# in_out.net
KiCad netlist of a schematic drawn in EAGLE
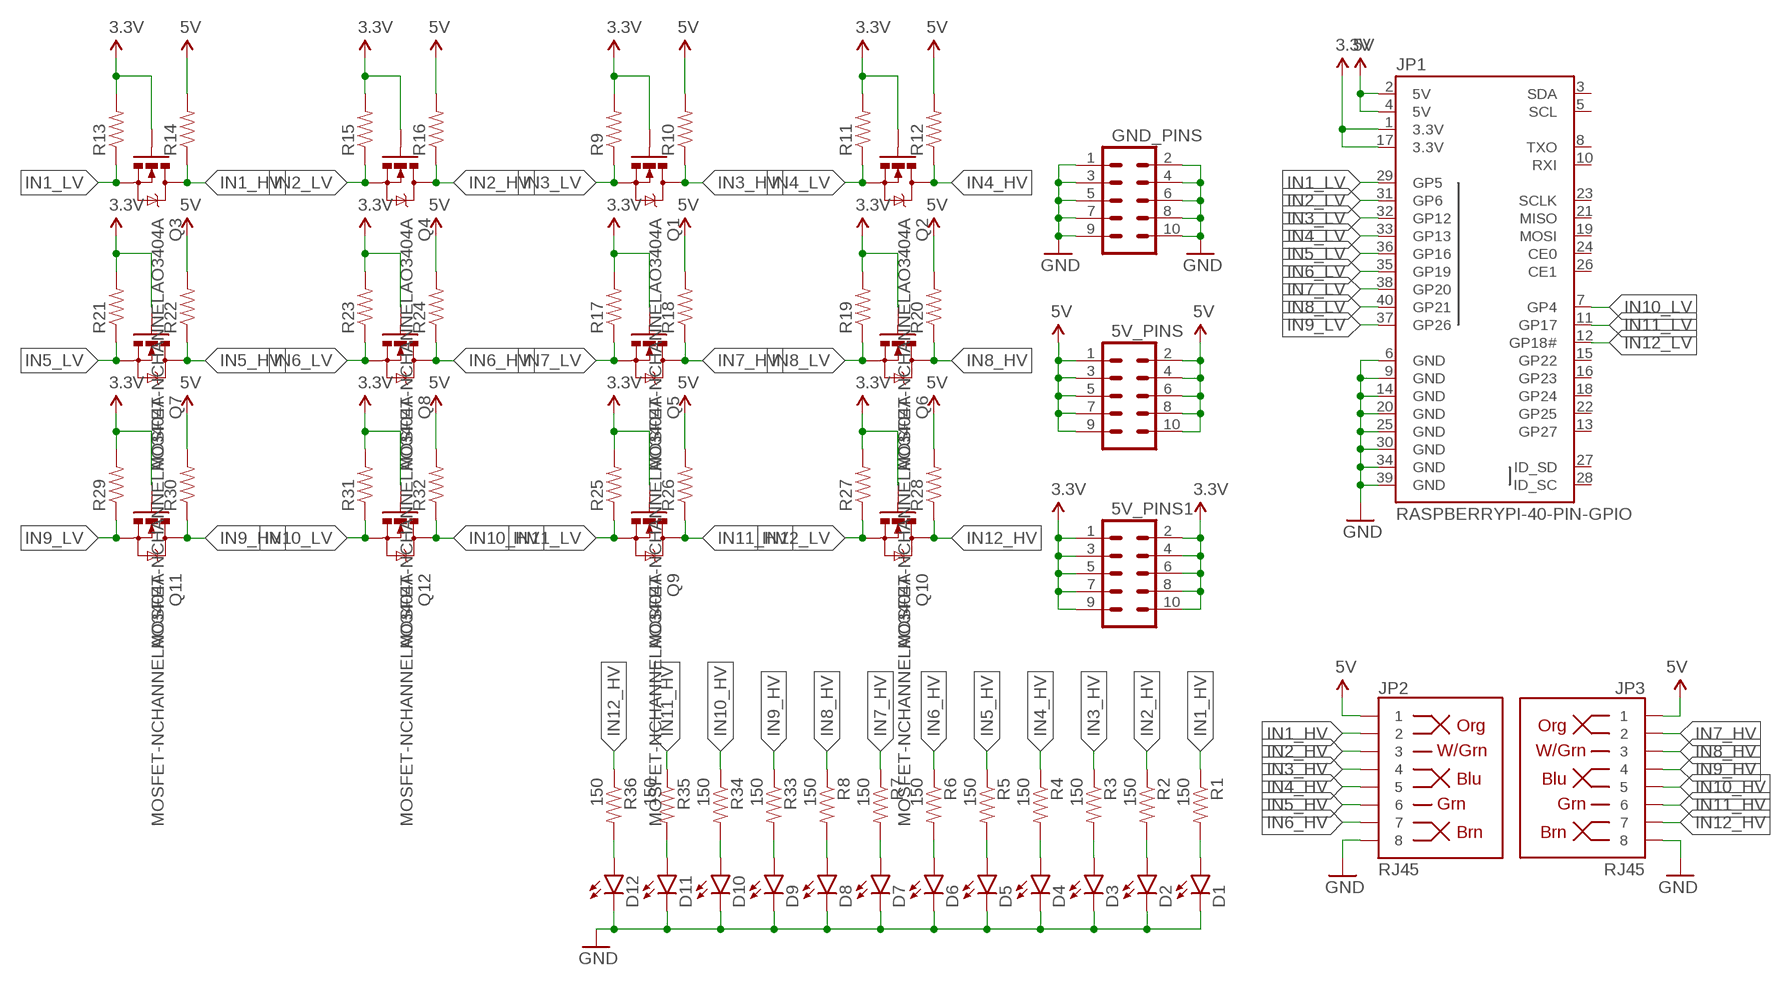
[diagram p0: schematic, sheet 1]

(export (version "E")
  (design (tool "Eeschema 10.0.6"))
  (components
    (comp (ref "5V_PINS")
      (value "M05X2PTH")
      (footprint "eagle-import:AVR_ICSP")
      (libsource (lib "eagle-import") (part "M05X2PTH"))
    )
    (comp (ref "5V_PINS1")
      (value "M05X2PTH")
      (footprint "eagle-import:AVR_ICSP")
      (libsource (lib "eagle-import") (part "M05X2PTH"))
    )
    (comp (ref "D1")
      (value "LED5MM")
      (footprint "eagle-import:LED5MM")
      (libsource (lib "eagle-import") (part "LED5MM"))
    )
    (comp (ref "D2")
      (value "LED5MM")
      (footprint "eagle-import:LED5MM")
      (libsource (lib "eagle-import") (part "LED5MM"))
    )
    (comp (ref "D3")
      (value "LED5MM")
      (footprint "eagle-import:LED5MM")
      (libsource (lib "eagle-import") (part "LED5MM"))
    )
    (comp (ref "D4")
      (value "LED5MM")
      (footprint "eagle-import:LED5MM")
      (libsource (lib "eagle-import") (part "LED5MM"))
    )
    (comp (ref "D5")
      (value "LED5MM")
      (footprint "eagle-import:LED5MM")
      (libsource (lib "eagle-import") (part "LED5MM"))
    )
    (comp (ref "D6")
      (value "LED5MM")
      (footprint "eagle-import:LED5MM")
      (libsource (lib "eagle-import") (part "LED5MM"))
    )
    (comp (ref "D7")
      (value "LED5MM")
      (footprint "eagle-import:LED5MM")
      (libsource (lib "eagle-import") (part "LED5MM"))
    )
    (comp (ref "D8")
      (value "LED5MM")
      (footprint "eagle-import:LED5MM")
      (libsource (lib "eagle-import") (part "LED5MM"))
    )
    (comp (ref "D9")
      (value "LED5MM")
      (footprint "eagle-import:LED5MM")
      (libsource (lib "eagle-import") (part "LED5MM"))
    )
    (comp (ref "D10")
      (value "LED5MM")
      (footprint "eagle-import:LED5MM")
      (libsource (lib "eagle-import") (part "LED5MM"))
    )
    (comp (ref "D11")
      (value "LED5MM")
      (footprint "eagle-import:LED5MM")
      (libsource (lib "eagle-import") (part "LED5MM"))
    )
    (comp (ref "D12")
      (value "LED5MM")
      (footprint "eagle-import:LED5MM")
      (libsource (lib "eagle-import") (part "LED5MM"))
    )
    (comp (ref "GND_PINS")
      (value "M05X2PTH")
      (footprint "eagle-import:AVR_ICSP")
      (libsource (lib "eagle-import") (part "M05X2PTH"))
    )
    (comp (ref "JP1")
      (value "RASPBERRYPI-40-PIN-GPIO")
      (footprint "eagle-import:2X20-SHROUDED")
      (libsource (lib "eagle-import") (part "RASPBERRYPI-40-PIN-GPIO"))
    )
    (comp (ref "JP2")
      (value "RJ45")
      (footprint "eagle-import:RJ45-8")
      (libsource (lib "eagle-import") (part "RJ45-8PTH"))
    )
    (comp (ref "JP3")
      (value "RJ45")
      (footprint "eagle-import:RJ45-8")
      (libsource (lib "eagle-import") (part "RJ45-8PTH"))
    )
    (comp (ref "Q1")
      (value "MOSFET-NCHANNELAO3404A")
      (footprint "eagle-import:SOT23-3")
      (libsource (lib "eagle-import") (part "MOSFET-NCHANNELAO3404A"))
    )
    (comp (ref "Q2")
      (value "MOSFET-NCHANNELAO3404A")
      (footprint "eagle-import:SOT23-3")
      (libsource (lib "eagle-import") (part "MOSFET-NCHANNELAO3404A"))
    )
    (comp (ref "Q3")
      (value "MOSFET-NCHANNELAO3404A")
      (footprint "eagle-import:SOT23-3")
      (libsource (lib "eagle-import") (part "MOSFET-NCHANNELAO3404A"))
    )
    (comp (ref "Q4")
      (value "MOSFET-NCHANNELAO3404A")
      (footprint "eagle-import:SOT23-3")
      (libsource (lib "eagle-import") (part "MOSFET-NCHANNELAO3404A"))
    )
    (comp (ref "Q5")
      (value "MOSFET-NCHANNELAO3404A")
      (footprint "eagle-import:SOT23-3")
      (libsource (lib "eagle-import") (part "MOSFET-NCHANNELAO3404A"))
    )
    (comp (ref "Q6")
      (value "MOSFET-NCHANNELAO3404A")
      (footprint "eagle-import:SOT23-3")
      (libsource (lib "eagle-import") (part "MOSFET-NCHANNELAO3404A"))
    )
    (comp (ref "Q7")
      (value "MOSFET-NCHANNELAO3404A")
      (footprint "eagle-import:SOT23-3")
      (libsource (lib "eagle-import") (part "MOSFET-NCHANNELAO3404A"))
    )
    (comp (ref "Q8")
      (value "MOSFET-NCHANNELAO3404A")
      (footprint "eagle-import:SOT23-3")
      (libsource (lib "eagle-import") (part "MOSFET-NCHANNELAO3404A"))
    )
    (comp (ref "Q9")
      (value "MOSFET-NCHANNELAO3404A")
      (footprint "eagle-import:SOT23-3")
      (libsource (lib "eagle-import") (part "MOSFET-NCHANNELAO3404A"))
    )
    (comp (ref "Q10")
      (value "MOSFET-NCHANNELAO3404A")
      (footprint "eagle-import:SOT23-3")
      (libsource (lib "eagle-import") (part "MOSFET-NCHANNELAO3404A"))
    )
    (comp (ref "Q11")
      (value "MOSFET-NCHANNELAO3404A")
      (footprint "eagle-import:SOT23-3")
      (libsource (lib "eagle-import") (part "MOSFET-NCHANNELAO3404A"))
    )
    (comp (ref "Q12")
      (value "MOSFET-NCHANNELAO3404A")
      (footprint "eagle-import:SOT23-3")
      (libsource (lib "eagle-import") (part "MOSFET-NCHANNELAO3404A"))
    )
    (comp (ref "R1")
      (value "150")
      (footprint "eagle-import:AXIAL-0.3EZ")
      (libsource (lib "eagle-import") (part "RESISTOREZ"))
    )
    (comp (ref "R2")
      (value "150")
      (footprint "eagle-import:AXIAL-0.3EZ")
      (libsource (lib "eagle-import") (part "RESISTOREZ"))
    )
    (comp (ref "R3")
      (value "150")
      (footprint "eagle-import:AXIAL-0.3EZ")
      (libsource (lib "eagle-import") (part "RESISTOREZ"))
    )
    (comp (ref "R4")
      (value "150")
      (footprint "eagle-import:AXIAL-0.3EZ")
      (libsource (lib "eagle-import") (part "RESISTOREZ"))
    )
    (comp (ref "R5")
      (value "150")
      (footprint "eagle-import:AXIAL-0.3EZ")
      (libsource (lib "eagle-import") (part "RESISTOREZ"))
    )
    (comp (ref "R6")
      (value "150")
      (footprint "eagle-import:AXIAL-0.3EZ")
      (libsource (lib "eagle-import") (part "RESISTOREZ"))
    )
    (comp (ref "R7")
      (value "150")
      (footprint "eagle-import:AXIAL-0.3EZ")
      (libsource (lib "eagle-import") (part "RESISTOREZ"))
    )
    (comp (ref "R8")
      (value "150")
      (footprint "eagle-import:AXIAL-0.3EZ")
      (libsource (lib "eagle-import") (part "RESISTOREZ"))
    )
    (comp (ref "R9")
      (value "RESISTORPTH-1/4W")
      (footprint "eagle-import:AXIAL-0.4")
      (libsource (lib "eagle-import") (part "RESISTORPTH-1/4W"))
    )
    (comp (ref "R10")
      (value "RESISTORPTH-1/4W")
      (footprint "eagle-import:AXIAL-0.4")
      (libsource (lib "eagle-import") (part "RESISTORPTH-1/4W"))
    )
    (comp (ref "R11")
      (value "RESISTORPTH-1/4W")
      (footprint "eagle-import:AXIAL-0.4")
      (libsource (lib "eagle-import") (part "RESISTORPTH-1/4W"))
    )
    (comp (ref "R12")
      (value "RESISTORPTH-1/4W")
      (footprint "eagle-import:AXIAL-0.4")
      (libsource (lib "eagle-import") (part "RESISTORPTH-1/4W"))
    )
    (comp (ref "R13")
      (value "RESISTORPTH-1/4W")
      (footprint "eagle-import:AXIAL-0.4")
      (libsource (lib "eagle-import") (part "RESISTORPTH-1/4W"))
    )
    (comp (ref "R14")
      (value "RESISTORPTH-1/4W")
      (footprint "eagle-import:AXIAL-0.4")
      (libsource (lib "eagle-import") (part "RESISTORPTH-1/4W"))
    )
    (comp (ref "R15")
      (value "RESISTORPTH-1/4W")
      (footprint "eagle-import:AXIAL-0.4")
      (libsource (lib "eagle-import") (part "RESISTORPTH-1/4W"))
    )
    (comp (ref "R16")
      (value "RESISTORPTH-1/4W")
      (footprint "eagle-import:AXIAL-0.4")
      (libsource (lib "eagle-import") (part "RESISTORPTH-1/4W"))
    )
    (comp (ref "R17")
      (value "RESISTORPTH-1/4W")
      (footprint "eagle-import:AXIAL-0.4")
      (libsource (lib "eagle-import") (part "RESISTORPTH-1/4W"))
    )
    (comp (ref "R18")
      (value "RESISTORPTH-1/4W")
      (footprint "eagle-import:AXIAL-0.4")
      (libsource (lib "eagle-import") (part "RESISTORPTH-1/4W"))
    )
    (comp (ref "R19")
      (value "RESISTORPTH-1/4W")
      (footprint "eagle-import:AXIAL-0.4")
      (libsource (lib "eagle-import") (part "RESISTORPTH-1/4W"))
    )
    (comp (ref "R20")
      (value "RESISTORPTH-1/4W")
      (footprint "eagle-import:AXIAL-0.4")
      (libsource (lib "eagle-import") (part "RESISTORPTH-1/4W"))
    )
    (comp (ref "R21")
      (value "RESISTORPTH-1/4W")
      (footprint "eagle-import:AXIAL-0.4")
      (libsource (lib "eagle-import") (part "RESISTORPTH-1/4W"))
    )
    (comp (ref "R22")
      (value "RESISTORPTH-1/4W")
      (footprint "eagle-import:AXIAL-0.4")
      (libsource (lib "eagle-import") (part "RESISTORPTH-1/4W"))
    )
    (comp (ref "R23")
      (value "RESISTORPTH-1/4W")
      (footprint "eagle-import:AXIAL-0.4")
      (libsource (lib "eagle-import") (part "RESISTORPTH-1/4W"))
    )
    (comp (ref "R24")
      (value "RESISTORPTH-1/4W")
      (footprint "eagle-import:AXIAL-0.4")
      (libsource (lib "eagle-import") (part "RESISTORPTH-1/4W"))
    )
    (comp (ref "R25")
      (value "RESISTORPTH-1/4W")
      (footprint "eagle-import:AXIAL-0.4")
      (libsource (lib "eagle-import") (part "RESISTORPTH-1/4W"))
    )
    (comp (ref "R26")
      (value "RESISTORPTH-1/4W")
      (footprint "eagle-import:AXIAL-0.4")
      (libsource (lib "eagle-import") (part "RESISTORPTH-1/4W"))
    )
    (comp (ref "R27")
      (value "RESISTORPTH-1/4W")
      (footprint "eagle-import:AXIAL-0.4")
      (libsource (lib "eagle-import") (part "RESISTORPTH-1/4W"))
    )
    (comp (ref "R28")
      (value "RESISTORPTH-1/4W")
      (footprint "eagle-import:AXIAL-0.4")
      (libsource (lib "eagle-import") (part "RESISTORPTH-1/4W"))
    )
    (comp (ref "R29")
      (value "RESISTORPTH-1/4W")
      (footprint "eagle-import:AXIAL-0.4")
      (libsource (lib "eagle-import") (part "RESISTORPTH-1/4W"))
    )
    (comp (ref "R30")
      (value "RESISTORPTH-1/4W")
      (footprint "eagle-import:AXIAL-0.4")
      (libsource (lib "eagle-import") (part "RESISTORPTH-1/4W"))
    )
    (comp (ref "R31")
      (value "RESISTORPTH-1/4W")
      (footprint "eagle-import:AXIAL-0.4")
      (libsource (lib "eagle-import") (part "RESISTORPTH-1/4W"))
    )
    (comp (ref "R32")
      (value "RESISTORPTH-1/4W")
      (footprint "eagle-import:AXIAL-0.4")
      (libsource (lib "eagle-import") (part "RESISTORPTH-1/4W"))
    )
    (comp (ref "R33")
      (value "150")
      (footprint "eagle-import:AXIAL-0.3EZ")
      (libsource (lib "eagle-import") (part "RESISTOREZ"))
    )
    (comp (ref "R34")
      (value "150")
      (footprint "eagle-import:AXIAL-0.3EZ")
      (libsource (lib "eagle-import") (part "RESISTOREZ"))
    )
    (comp (ref "R35")
      (value "150")
      (footprint "eagle-import:AXIAL-0.3EZ")
      (libsource (lib "eagle-import") (part "RESISTOREZ"))
    )
    (comp (ref "R36")
      (value "150")
      (footprint "eagle-import:AXIAL-0.3EZ")
      (libsource (lib "eagle-import") (part "RESISTOREZ"))
    )
  )
  (nets
    (net (code "1") (name "3.3V") (class "Default")
      (node (ref "5V_PINS1") (pin "1") (pinfunction "1_1") (pintype "passive"))
      (node (ref "5V_PINS1") (pin "10") (pinfunction "10_10") (pintype "passive"))
      (node (ref "5V_PINS1") (pin "2") (pinfunction "2_2") (pintype "passive"))
      (node (ref "5V_PINS1") (pin "3") (pinfunction "3_3") (pintype "passive"))
      (node (ref "5V_PINS1") (pin "4") (pinfunction "4_4") (pintype "passive"))
      (node (ref "5V_PINS1") (pin "5") (pinfunction "5_5") (pintype "passive"))
      (node (ref "5V_PINS1") (pin "6") (pinfunction "6_6") (pintype "passive"))
      (node (ref "5V_PINS1") (pin "7") (pinfunction "7_7") (pintype "passive"))
      (node (ref "5V_PINS1") (pin "8") (pinfunction "8_8") (pintype "passive"))
      (node (ref "5V_PINS1") (pin "9") (pinfunction "9_9") (pintype "passive"))
      (node (ref "JP1") (pin "1") (pinfunction "3.3V_1") (pintype "power_in"))
      (node (ref "JP1") (pin "17") (pinfunction "3.3V_17") (pintype "power_in"))
      (node (ref "Q1") (pin "1") (pinfunction "G_1") (pintype "passive"))
      (node (ref "Q10") (pin "1") (pinfunction "G_1") (pintype "passive"))
      (node (ref "Q11") (pin "1") (pinfunction "G_1") (pintype "passive"))
      (node (ref "Q12") (pin "1") (pinfunction "G_1") (pintype "passive"))
      (node (ref "Q2") (pin "1") (pinfunction "G_1") (pintype "passive"))
      (node (ref "Q3") (pin "1") (pinfunction "G_1") (pintype "passive"))
      (node (ref "Q4") (pin "1") (pinfunction "G_1") (pintype "passive"))
      (node (ref "Q5") (pin "1") (pinfunction "G_1") (pintype "passive"))
      (node (ref "Q6") (pin "1") (pinfunction "G_1") (pintype "passive"))
      (node (ref "Q7") (pin "1") (pinfunction "G_1") (pintype "passive"))
      (node (ref "Q8") (pin "1") (pinfunction "G_1") (pintype "passive"))
      (node (ref "Q9") (pin "1") (pinfunction "G_1") (pintype "passive"))
      (node (ref "R11") (pin "P$2") (pinfunction "2_P$2") (pintype "passive"))
      (node (ref "R13") (pin "P$2") (pinfunction "2_P$2") (pintype "passive"))
      (node (ref "R15") (pin "P$2") (pinfunction "2_P$2") (pintype "passive"))
      (node (ref "R17") (pin "P$2") (pinfunction "2_P$2") (pintype "passive"))
      (node (ref "R19") (pin "P$2") (pinfunction "2_P$2") (pintype "passive"))
      (node (ref "R21") (pin "P$2") (pinfunction "2_P$2") (pintype "passive"))
      (node (ref "R23") (pin "P$2") (pinfunction "2_P$2") (pintype "passive"))
      (node (ref "R25") (pin "P$2") (pinfunction "2_P$2") (pintype "passive"))
      (node (ref "R27") (pin "P$2") (pinfunction "2_P$2") (pintype "passive"))
      (node (ref "R29") (pin "P$2") (pinfunction "2_P$2") (pintype "passive"))
      (node (ref "R31") (pin "P$2") (pinfunction "2_P$2") (pintype "passive"))
      (node (ref "R9") (pin "P$2") (pinfunction "2_P$2") (pintype "passive"))
    )
    (net (code "2") (name "5V") (class "Default")
      (node (ref "5V_PINS") (pin "1") (pinfunction "1_1") (pintype "passive"))
      (node (ref "5V_PINS") (pin "10") (pinfunction "10_10") (pintype "passive"))
      (node (ref "5V_PINS") (pin "2") (pinfunction "2_2") (pintype "passive"))
      (node (ref "5V_PINS") (pin "3") (pinfunction "3_3") (pintype "passive"))
      (node (ref "5V_PINS") (pin "4") (pinfunction "4_4") (pintype "passive"))
      (node (ref "5V_PINS") (pin "5") (pinfunction "5_5") (pintype "passive"))
      (node (ref "5V_PINS") (pin "6") (pinfunction "6_6") (pintype "passive"))
      (node (ref "5V_PINS") (pin "7") (pinfunction "7_7") (pintype "passive"))
      (node (ref "5V_PINS") (pin "8") (pinfunction "8_8") (pintype "passive"))
      (node (ref "5V_PINS") (pin "9") (pinfunction "9_9") (pintype "passive"))
      (node (ref "JP1") (pin "2") (pinfunction "5V_2") (pintype "power_in"))
      (node (ref "JP1") (pin "4") (pinfunction "5V_4") (pintype "power_in"))
      (node (ref "JP2") (pin "1") (pinfunction "1_1") (pintype "bidirectional"))
      (node (ref "JP3") (pin "1") (pinfunction "1_1") (pintype "bidirectional"))
      (node (ref "R10") (pin "P$2") (pinfunction "2_P$2") (pintype "passive"))
      (node (ref "R12") (pin "P$2") (pinfunction "2_P$2") (pintype "passive"))
      (node (ref "R14") (pin "P$2") (pinfunction "2_P$2") (pintype "passive"))
      (node (ref "R16") (pin "P$2") (pinfunction "2_P$2") (pintype "passive"))
      (node (ref "R18") (pin "P$2") (pinfunction "2_P$2") (pintype "passive"))
      (node (ref "R20") (pin "P$2") (pinfunction "2_P$2") (pintype "passive"))
      (node (ref "R22") (pin "P$2") (pinfunction "2_P$2") (pintype "passive"))
      (node (ref "R24") (pin "P$2") (pinfunction "2_P$2") (pintype "passive"))
      (node (ref "R26") (pin "P$2") (pinfunction "2_P$2") (pintype "passive"))
      (node (ref "R28") (pin "P$2") (pinfunction "2_P$2") (pintype "passive"))
      (node (ref "R30") (pin "P$2") (pinfunction "2_P$2") (pintype "passive"))
      (node (ref "R32") (pin "P$2") (pinfunction "2_P$2") (pintype "passive"))
    )
    (net (code "3") (name "GND") (class "Default")
      (node (ref "D1") (pin "K") (pinfunction "C_K") (pintype "passive"))
      (node (ref "D10") (pin "K") (pinfunction "C_K") (pintype "passive"))
      (node (ref "D11") (pin "K") (pinfunction "C_K") (pintype "passive"))
      (node (ref "D12") (pin "K") (pinfunction "C_K") (pintype "passive"))
      (node (ref "D2") (pin "K") (pinfunction "C_K") (pintype "passive"))
      (node (ref "D3") (pin "K") (pinfunction "C_K") (pintype "passive"))
      (node (ref "D4") (pin "K") (pinfunction "C_K") (pintype "passive"))
      (node (ref "D5") (pin "K") (pinfunction "C_K") (pintype "passive"))
      (node (ref "D6") (pin "K") (pinfunction "C_K") (pintype "passive"))
      (node (ref "D7") (pin "K") (pinfunction "C_K") (pintype "passive"))
      (node (ref "D8") (pin "K") (pinfunction "C_K") (pintype "passive"))
      (node (ref "D9") (pin "K") (pinfunction "C_K") (pintype "passive"))
      (node (ref "GND_PINS") (pin "1") (pinfunction "1_1") (pintype "passive"))
      (node (ref "GND_PINS") (pin "10") (pinfunction "10_10") (pintype "passive"))
      (node (ref "GND_PINS") (pin "2") (pinfunction "2_2") (pintype "passive"))
      (node (ref "GND_PINS") (pin "3") (pinfunction "3_3") (pintype "passive"))
      (node (ref "GND_PINS") (pin "4") (pinfunction "4_4") (pintype "passive"))
      (node (ref "GND_PINS") (pin "5") (pinfunction "5_5") (pintype "passive"))
      (node (ref "GND_PINS") (pin "6") (pinfunction "6_6") (pintype "passive"))
      (node (ref "GND_PINS") (pin "7") (pinfunction "7_7") (pintype "passive"))
      (node (ref "GND_PINS") (pin "8") (pinfunction "8_8") (pintype "passive"))
      (node (ref "GND_PINS") (pin "9") (pinfunction "9_9") (pintype "passive"))
      (node (ref "JP1") (pin "14") (pinfunction "GND_14") (pintype "power_in"))
      (node (ref "JP1") (pin "20") (pinfunction "GND_20") (pintype "power_in"))
      (node (ref "JP1") (pin "25") (pinfunction "GND_25") (pintype "power_in"))
      (node (ref "JP1") (pin "30") (pinfunction "GND_30") (pintype "power_in"))
      (node (ref "JP1") (pin "34") (pinfunction "GND_34") (pintype "power_in"))
      (node (ref "JP1") (pin "39") (pinfunction "GND_39") (pintype "power_in"))
      (node (ref "JP1") (pin "6") (pinfunction "GND_6") (pintype "power_in"))
      (node (ref "JP1") (pin "9") (pinfunction "GND_9") (pintype "power_in"))
      (node (ref "JP2") (pin "8") (pinfunction "8_8") (pintype "bidirectional"))
      (node (ref "JP3") (pin "8") (pinfunction "8_8") (pintype "bidirectional"))
    )
    (net (code "4") (name "IN1_HV") (class "Default")
      (node (ref "JP2") (pin "2") (pinfunction "2_2") (pintype "bidirectional"))
      (node (ref "Q3") (pin "3") (pinfunction "D_3") (pintype "passive"))
      (node (ref "R1") (pin "P$1") (pinfunction "1_P$1") (pintype "passive"))
      (node (ref "R14") (pin "P$1") (pinfunction "1_P$1") (pintype "passive"))
    )
    (net (code "5") (name "IN1_LV") (class "Default")
      (node (ref "JP1") (pin "29") (pinfunction "GP5_29") (pintype "bidirectional"))
      (node (ref "Q3") (pin "2") (pinfunction "S_2") (pintype "passive"))
      (node (ref "R13") (pin "P$1") (pinfunction "1_P$1") (pintype "passive"))
    )
    (net (code "6") (name "IN2_HV") (class "Default")
      (node (ref "JP2") (pin "3") (pinfunction "3_3") (pintype "bidirectional"))
      (node (ref "Q4") (pin "3") (pinfunction "D_3") (pintype "passive"))
      (node (ref "R16") (pin "P$1") (pinfunction "1_P$1") (pintype "passive"))
      (node (ref "R2") (pin "P$1") (pinfunction "1_P$1") (pintype "passive"))
    )
    (net (code "7") (name "IN2_LV") (class "Default")
      (node (ref "JP1") (pin "31") (pinfunction "GP6_31") (pintype "bidirectional"))
      (node (ref "Q4") (pin "2") (pinfunction "S_2") (pintype "passive"))
      (node (ref "R15") (pin "P$1") (pinfunction "1_P$1") (pintype "passive"))
    )
    (net (code "8") (name "IN3_HV") (class "Default")
      (node (ref "JP2") (pin "4") (pinfunction "4_4") (pintype "bidirectional"))
      (node (ref "Q1") (pin "3") (pinfunction "D_3") (pintype "passive"))
      (node (ref "R10") (pin "P$1") (pinfunction "1_P$1") (pintype "passive"))
      (node (ref "R3") (pin "P$1") (pinfunction "1_P$1") (pintype "passive"))
    )
    (net (code "9") (name "IN3_LV") (class "Default")
      (node (ref "JP1") (pin "32") (pinfunction "GP12_32") (pintype "bidirectional"))
      (node (ref "Q1") (pin "2") (pinfunction "S_2") (pintype "passive"))
      (node (ref "R9") (pin "P$1") (pinfunction "1_P$1") (pintype "passive"))
    )
    (net (code "10") (name "IN4_HV") (class "Default")
      (node (ref "JP2") (pin "5") (pinfunction "5_5") (pintype "bidirectional"))
      (node (ref "Q2") (pin "3") (pinfunction "D_3") (pintype "passive"))
      (node (ref "R12") (pin "P$1") (pinfunction "1_P$1") (pintype "passive"))
      (node (ref "R4") (pin "P$1") (pinfunction "1_P$1") (pintype "passive"))
    )
    (net (code "11") (name "IN4_LV") (class "Default")
      (node (ref "JP1") (pin "33") (pinfunction "GP13_33") (pintype "bidirectional"))
      (node (ref "Q2") (pin "2") (pinfunction "S_2") (pintype "passive"))
      (node (ref "R11") (pin "P$1") (pinfunction "1_P$1") (pintype "passive"))
    )
    (net (code "12") (name "IN5_HV") (class "Default")
      (node (ref "JP2") (pin "6") (pinfunction "6_6") (pintype "bidirectional"))
      (node (ref "Q7") (pin "3") (pinfunction "D_3") (pintype "passive"))
      (node (ref "R22") (pin "P$1") (pinfunction "1_P$1") (pintype "passive"))
      (node (ref "R5") (pin "P$1") (pinfunction "1_P$1") (pintype "passive"))
    )
    (net (code "13") (name "IN5_LV") (class "Default")
      (node (ref "JP1") (pin "36") (pinfunction "GP16_36") (pintype "bidirectional"))
      (node (ref "Q7") (pin "2") (pinfunction "S_2") (pintype "passive"))
      (node (ref "R21") (pin "P$1") (pinfunction "1_P$1") (pintype "passive"))
    )
    (net (code "14") (name "IN6_HV") (class "Default")
      (node (ref "JP2") (pin "7") (pinfunction "7_7") (pintype "bidirectional"))
      (node (ref "Q8") (pin "3") (pinfunction "D_3") (pintype "passive"))
      (node (ref "R24") (pin "P$1") (pinfunction "1_P$1") (pintype "passive"))
      (node (ref "R6") (pin "P$1") (pinfunction "1_P$1") (pintype "passive"))
    )
    (net (code "15") (name "IN6_LV") (class "Default")
      (node (ref "JP1") (pin "35") (pinfunction "GP19_35") (pintype "bidirectional"))
      (node (ref "Q8") (pin "2") (pinfunction "S_2") (pintype "passive"))
      (node (ref "R23") (pin "P$1") (pinfunction "1_P$1") (pintype "passive"))
    )
    (net (code "16") (name "IN7_HV") (class "Default")
      (node (ref "JP3") (pin "2") (pinfunction "2_2") (pintype "bidirectional"))
      (node (ref "Q5") (pin "3") (pinfunction "D_3") (pintype "passive"))
      (node (ref "R18") (pin "P$1") (pinfunction "1_P$1") (pintype "passive"))
      (node (ref "R7") (pin "P$1") (pinfunction "1_P$1") (pintype "passive"))
    )
    (net (code "17") (name "IN7_LV") (class "Default")
      (node (ref "JP1") (pin "38") (pinfunction "GP20_38") (pintype "bidirectional"))
      (node (ref "Q5") (pin "2") (pinfunction "S_2") (pintype "passive"))
      (node (ref "R17") (pin "P$1") (pinfunction "1_P$1") (pintype "passive"))
    )
    (net (code "18") (name "IN8_HV") (class "Default")
      (node (ref "JP3") (pin "3") (pinfunction "3_3") (pintype "bidirectional"))
      (node (ref "Q6") (pin "3") (pinfunction "D_3") (pintype "passive"))
      (node (ref "R20") (pin "P$1") (pinfunction "1_P$1") (pintype "passive"))
      (node (ref "R8") (pin "P$1") (pinfunction "1_P$1") (pintype "passive"))
    )
    (net (code "19") (name "IN8_LV") (class "Default")
      (node (ref "JP1") (pin "40") (pinfunction "GP21_40") (pintype "bidirectional"))
      (node (ref "Q6") (pin "2") (pinfunction "S_2") (pintype "passive"))
      (node (ref "R19") (pin "P$1") (pinfunction "1_P$1") (pintype "passive"))
    )
    (net (code "20") (name "IN9_HV") (class "Default")
      (node (ref "JP3") (pin "4") (pinfunction "4_4") (pintype "bidirectional"))
      (node (ref "Q11") (pin "3") (pinfunction "D_3") (pintype "passive"))
      (node (ref "R30") (pin "P$1") (pinfunction "1_P$1") (pintype "passive"))
      (node (ref "R33") (pin "P$1") (pinfunction "1_P$1") (pintype "passive"))
    )
    (net (code "21") (name "IN9_LV") (class "Default")
      (node (ref "JP1") (pin "37") (pinfunction "GP26_37") (pintype "bidirectional"))
      (node (ref "Q11") (pin "2") (pinfunction "S_2") (pintype "passive"))
      (node (ref "R29") (pin "P$1") (pinfunction "1_P$1") (pintype "passive"))
    )
    (net (code "22") (name "IN10_HV") (class "Default")
      (node (ref "JP3") (pin "5") (pinfunction "5_5") (pintype "bidirectional"))
      (node (ref "Q12") (pin "3") (pinfunction "D_3") (pintype "passive"))
      (node (ref "R32") (pin "P$1") (pinfunction "1_P$1") (pintype "passive"))
      (node (ref "R34") (pin "P$1") (pinfunction "1_P$1") (pintype "passive"))
    )
    (net (code "23") (name "IN10_LV") (class "Default")
      (node (ref "JP1") (pin "7") (pinfunction "GP4_7") (pintype "bidirectional"))
      (node (ref "Q12") (pin "2") (pinfunction "S_2") (pintype "passive"))
      (node (ref "R31") (pin "P$1") (pinfunction "1_P$1") (pintype "passive"))
    )
    (net (code "24") (name "IN11_HV") (class "Default")
      (node (ref "JP3") (pin "6") (pinfunction "6_6") (pintype "bidirectional"))
      (node (ref "Q9") (pin "3") (pinfunction "D_3") (pintype "passive"))
      (node (ref "R26") (pin "P$1") (pinfunction "1_P$1") (pintype "passive"))
      (node (ref "R35") (pin "P$1") (pinfunction "1_P$1") (pintype "passive"))
    )
    (net (code "25") (name "IN11_LV") (class "Default")
      (node (ref "JP1") (pin "11") (pinfunction "GP17_11") (pintype "bidirectional"))
      (node (ref "Q9") (pin "2") (pinfunction "S_2") (pintype "passive"))
      (node (ref "R25") (pin "P$1") (pinfunction "1_P$1") (pintype "passive"))
    )
    (net (code "26") (name "IN12_HV") (class "Default")
      (node (ref "JP3") (pin "7") (pinfunction "7_7") (pintype "bidirectional"))
      (node (ref "Q10") (pin "3") (pinfunction "D_3") (pintype "passive"))
      (node (ref "R28") (pin "P$1") (pinfunction "1_P$1") (pintype "passive"))
      (node (ref "R36") (pin "P$1") (pinfunction "1_P$1") (pintype "passive"))
    )
    (net (code "27") (name "IN12_LV") (class "Default")
      (node (ref "JP1") (pin "12") (pinfunction "GP18#_12") (pintype "bidirectional"))
      (node (ref "Q10") (pin "2") (pinfunction "S_2") (pintype "passive"))
      (node (ref "R27") (pin "P$1") (pinfunction "1_P$1") (pintype "passive"))
    )
    (net (code "28") (name "Net-(R1-2)") (class "Default")
      (node (ref "D1") (pin "A") (pinfunction "A_A") (pintype "passive"))
      (node (ref "R1") (pin "P$2") (pinfunction "2_P$2") (pintype "passive"))
    )
    (net (code "29") (name "Net-(R2-2)") (class "Default")
      (node (ref "D2") (pin "A") (pinfunction "A_A") (pintype "passive"))
      (node (ref "R2") (pin "P$2") (pinfunction "2_P$2") (pintype "passive"))
    )
    (net (code "30") (name "Net-(R3-2)") (class "Default")
      (node (ref "D3") (pin "A") (pinfunction "A_A") (pintype "passive"))
      (node (ref "R3") (pin "P$2") (pinfunction "2_P$2") (pintype "passive"))
    )
    (net (code "31") (name "Net-(R4-2)") (class "Default")
      (node (ref "D4") (pin "A") (pinfunction "A_A") (pintype "passive"))
      (node (ref "R4") (pin "P$2") (pinfunction "2_P$2") (pintype "passive"))
    )
    (net (code "32") (name "Net-(R5-2)") (class "Default")
      (node (ref "D5") (pin "A") (pinfunction "A_A") (pintype "passive"))
      (node (ref "R5") (pin "P$2") (pinfunction "2_P$2") (pintype "passive"))
    )
    (net (code "33") (name "Net-(R6-2)") (class "Default")
      (node (ref "D6") (pin "A") (pinfunction "A_A") (pintype "passive"))
      (node (ref "R6") (pin "P$2") (pinfunction "2_P$2") (pintype "passive"))
    )
    (net (code "34") (name "Net-(R7-2)") (class "Default")
      (node (ref "D7") (pin "A") (pinfunction "A_A") (pintype "passive"))
      (node (ref "R7") (pin "P$2") (pinfunction "2_P$2") (pintype "passive"))
    )
    (net (code "35") (name "Net-(R8-2)") (class "Default")
      (node (ref "D8") (pin "A") (pinfunction "A_A") (pintype "passive"))
      (node (ref "R8") (pin "P$2") (pinfunction "2_P$2") (pintype "passive"))
    )
    (net (code "36") (name "Net-(R33-2)") (class "Default")
      (node (ref "D9") (pin "A") (pinfunction "A_A") (pintype "passive"))
      (node (ref "R33") (pin "P$2") (pinfunction "2_P$2") (pintype "passive"))
    )
    (net (code "37") (name "Net-(R34-2)") (class "Default")
      (node (ref "D10") (pin "A") (pinfunction "A_A") (pintype "passive"))
      (node (ref "R34") (pin "P$2") (pinfunction "2_P$2") (pintype "passive"))
    )
    (net (code "38") (name "Net-(R35-2)") (class "Default")
      (node (ref "D11") (pin "A") (pinfunction "A_A") (pintype "passive"))
      (node (ref "R35") (pin "P$2") (pinfunction "2_P$2") (pintype "passive"))
    )
    (net (code "39") (name "Net-(R36-2)") (class "Default")
      (node (ref "D12") (pin "A") (pinfunction "A_A") (pintype "passive"))
      (node (ref "R36") (pin "P$2") (pinfunction "2_P$2") (pintype "passive"))
    )
    (net (code "40") (name "unconnected-(JP1-CE0-Pad24)") (class "Default")
      (node (ref "JP1") (pin "24") (pinfunction "CE0_24") (pintype "output"))
    )
    (net (code "41") (name "unconnected-(JP1-CE1-Pad26)") (class "Default")
      (node (ref "JP1") (pin "26") (pinfunction "CE1_26") (pintype "output"))
    )
    (net (code "42") (name "unconnected-(JP1-GP22-Pad15)") (class "Default")
      (node (ref "JP1") (pin "15") (pinfunction "GP22_15") (pintype "bidirectional"))
    )
    (net (code "43") (name "unconnected-(JP1-GP23-Pad16)") (class "Default")
      (node (ref "JP1") (pin "16") (pinfunction "GP23_16") (pintype "bidirectional"))
    )
    (net (code "44") (name "unconnected-(JP1-GP24-Pad18)") (class "Default")
      (node (ref "JP1") (pin "18") (pinfunction "GP24_18") (pintype "bidirectional"))
    )
    (net (code "45") (name "unconnected-(JP1-GP25-Pad22)") (class "Default")
      (node (ref "JP1") (pin "22") (pinfunction "GP25_22") (pintype "bidirectional"))
    )
    (net (code "46") (name "unconnected-(JP1-GP27-Pad13)") (class "Default")
      (node (ref "JP1") (pin "13") (pinfunction "GP27_13") (pintype "bidirectional"))
    )
    (net (code "47") (name "unconnected-(JP1-ID_SC-Pad28)") (class "Default")
      (node (ref "JP1") (pin "28") (pinfunction "ID_SC_28") (pintype "bidirectional"))
    )
    (net (code "48") (name "unconnected-(JP1-ID_SD-Pad27)") (class "Default")
      (node (ref "JP1") (pin "27") (pinfunction "ID_SD_27") (pintype "bidirectional"))
    )
    (net (code "49") (name "unconnected-(JP1-MISO-Pad21)") (class "Default")
      (node (ref "JP1") (pin "21") (pinfunction "MISO_21") (pintype "input"))
    )
    (net (code "50") (name "unconnected-(JP1-MOSI-Pad19)") (class "Default")
      (node (ref "JP1") (pin "19") (pinfunction "MOSI_19") (pintype "output"))
    )
    (net (code "51") (name "unconnected-(JP1-RXI-Pad10)") (class "Default")
      (node (ref "JP1") (pin "10") (pinfunction "RXI_10") (pintype "input"))
    )
    (net (code "52") (name "unconnected-(JP1-SCL-Pad5)") (class "Default")
      (node (ref "JP1") (pin "5") (pinfunction "SCL_5") (pintype "bidirectional"))
    )
    (net (code "53") (name "unconnected-(JP1-SCLK-Pad23)") (class "Default")
      (node (ref "JP1") (pin "23") (pinfunction "SCLK_23") (pintype "output"))
    )
    (net (code "54") (name "unconnected-(JP1-SDA-Pad3)") (class "Default")
      (node (ref "JP1") (pin "3") (pinfunction "SDA_3") (pintype "bidirectional"))
    )
    (net (code "55") (name "unconnected-(JP1-TXO-Pad8)") (class "Default")
      (node (ref "JP1") (pin "8") (pinfunction "TXO_8") (pintype "output"))
    )
  )
)
